# 7segement4digits1badidea-mk-2_0.net
KiCad netlist of a schematic drawn in EAGLE
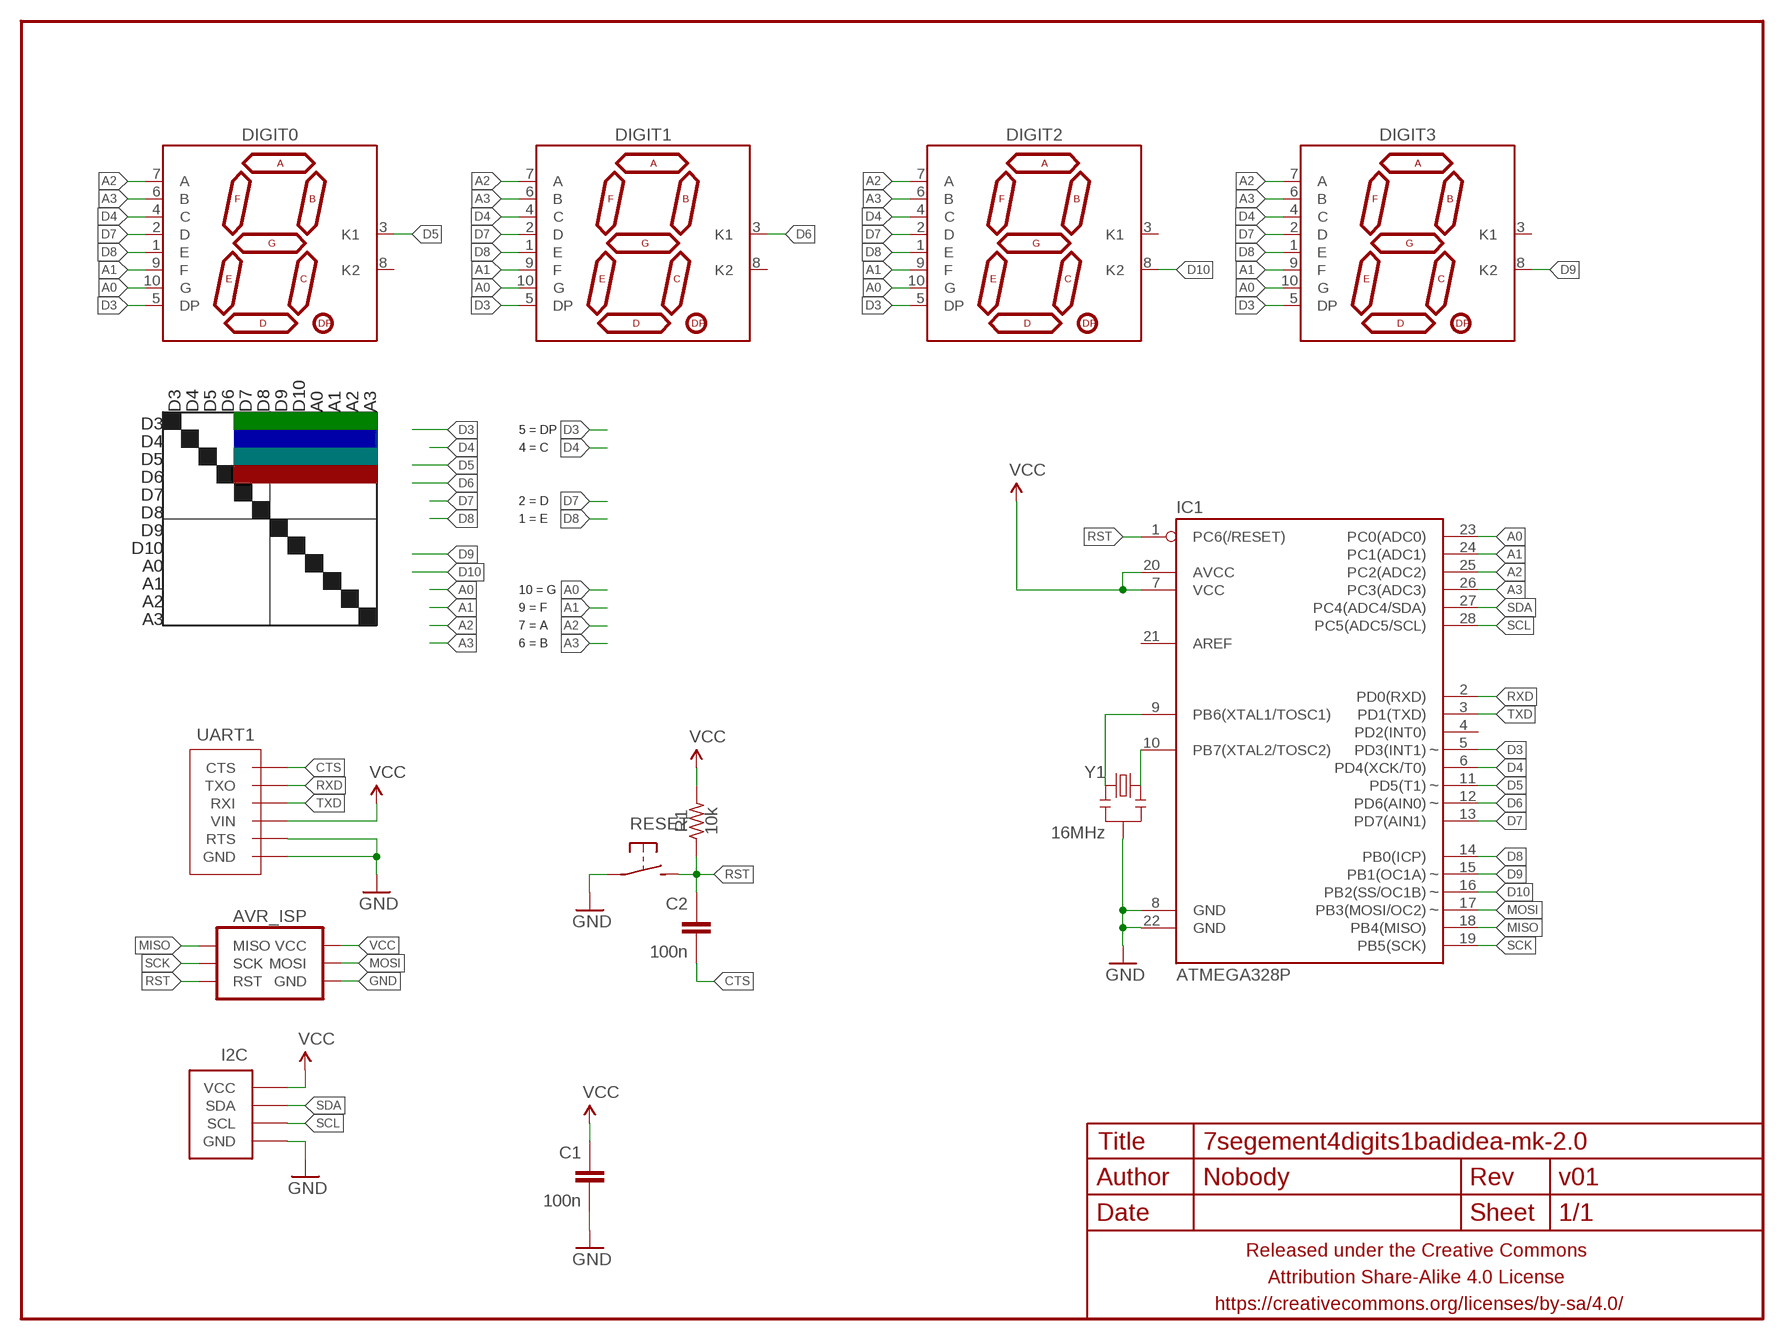
[diagram p0: schematic, sheet 1]

(export (version "E")
  (design (tool "Eeschema 10.0.6"))
  (components
    (comp (ref "AVR_ISP")
      (value "AVR_SPI_PRG_6PTH")
      (footprint "eagle-import:2X3")
      (libsource (lib "eagle-import") (part "AVR_SPI_PRG_6PTH"))
    )
    (comp (ref "C1")
      (value "100n")
      (footprint "eagle-import:C025-024X044")
      (libsource (lib "eagle-import") (part "CAPACITOR-CERAMIC025-024X044"))
    )
    (comp (ref "C2")
      (value "100n")
      (footprint "eagle-import:C025-024X044")
      (libsource (lib "eagle-import") (part "CAPACITOR-CERAMIC025-024X044"))
    )
    (comp (ref "DIGIT0")
      (value "7SEG_1DIGPTH-25.4MM")
      (footprint "eagle-import:7SEG_1DIG_25.4MM")
      (libsource (lib "eagle-import") (part "7SEG_1DIGPTH-25.4MM"))
    )
    (comp (ref "DIGIT1")
      (value "7SEG_1DIGPTH-25.4MM")
      (footprint "eagle-import:7SEG_1DIG_25.4MM")
      (libsource (lib "eagle-import") (part "7SEG_1DIGPTH-25.4MM"))
    )
    (comp (ref "DIGIT2")
      (value "7SEG_1DIGPTH-25.4MM")
      (footprint "eagle-import:7SEG_1DIG_25.4MM")
      (libsource (lib "eagle-import") (part "7SEG_1DIGPTH-25.4MM"))
    )
    (comp (ref "DIGIT3")
      (value "7SEG_1DIGPTH-25.4MM")
      (footprint "eagle-import:7SEG_1DIG_25.4MM")
      (libsource (lib "eagle-import") (part "7SEG_1DIGPTH-25.4MM"))
    )
    (comp (ref "FRAME1")
      (value "FRAME-LETTERNO_PACKAGE")
      (footprint "eagle-import:DUMMY")
      (fields (field (name "DESIGNER") "Nobody"))
      (libsource (lib "eagle-import") (part "FRAME-LETTERNO_PACKAGE"))
    )
    (comp (ref "I2C")
      (value "M04-I2CPTH-0.1IN-CENTERED-FLIPPED")
      (footprint "eagle-import:1X04-PTH-VERT-I2C-CENTERED-FLIPPED")
      (libsource (lib "eagle-import") (part "M04-I2CPTH-0.1IN-CENTERED-FLIPPED"))
    )
    (comp (ref "IC1")
      (value "ATMEGA328P")
      (footprint "eagle-import:DIL28-3")
      (libsource (lib "eagle-import") (part "ATMEGA328P_PDIP"))
    )
    (comp (ref "R1")
      (value "10k")
      (footprint "eagle-import:RESISTOR-AXIAL-PTH-7.62MM")
      (libsource (lib "eagle-import") (part "RESISTORPTH-AXIAL-7.62MM"))
    )
    (comp (ref "RESET")
      (value "SPST-NO-TACT3MM-PTH-SMALL-PADS")
      (footprint "eagle-import:DTS-3-SMALL-PADS")
      (libsource (lib "eagle-import") (part "SPST-NO-TACT3MM-PTH-SMALL-PADS"))
    )
    (comp (ref "UART1")
      (value "M06-UARTPTH-0.1IN")
      (footprint "eagle-import:1X06_PTH_UART")
      (libsource (lib "eagle-import") (part "M06-UARTPTH-0.1IN"))
    )
    (comp (ref "Y1")
      (value "16MHz")
      (footprint "eagle-import:RESONATOR-PTH")
      (libsource (lib "eagle-import") (part "RESONATORPTH"))
    )
  )
  (nets
    (net (code "1") (name "A0") (class "Default")
      (node (ref "DIGIT0") (pin "10") (pinfunction "G_10") (pintype "bidirectional"))
      (node (ref "DIGIT1") (pin "10") (pinfunction "G_10") (pintype "bidirectional"))
      (node (ref "DIGIT2") (pin "10") (pinfunction "G_10") (pintype "bidirectional"))
      (node (ref "DIGIT3") (pin "10") (pinfunction "G_10") (pintype "bidirectional"))
      (node (ref "IC1") (pin "23") (pinfunction "PC0(ADC0)_23") (pintype "bidirectional"))
    )
    (net (code "2") (name "A1") (class "Default")
      (node (ref "DIGIT0") (pin "9") (pinfunction "F_9") (pintype "bidirectional"))
      (node (ref "DIGIT1") (pin "9") (pinfunction "F_9") (pintype "bidirectional"))
      (node (ref "DIGIT2") (pin "9") (pinfunction "F_9") (pintype "bidirectional"))
      (node (ref "DIGIT3") (pin "9") (pinfunction "F_9") (pintype "bidirectional"))
      (node (ref "IC1") (pin "24") (pinfunction "PC1(ADC1)_24") (pintype "bidirectional"))
    )
    (net (code "3") (name "A2") (class "Default")
      (node (ref "DIGIT0") (pin "7") (pinfunction "A_7") (pintype "bidirectional"))
      (node (ref "DIGIT1") (pin "7") (pinfunction "A_7") (pintype "bidirectional"))
      (node (ref "DIGIT2") (pin "7") (pinfunction "A_7") (pintype "bidirectional"))
      (node (ref "DIGIT3") (pin "7") (pinfunction "A_7") (pintype "bidirectional"))
      (node (ref "IC1") (pin "25") (pinfunction "PC2(ADC2)_25") (pintype "bidirectional"))
    )
    (net (code "4") (name "A3") (class "Default")
      (node (ref "DIGIT0") (pin "6") (pinfunction "B_6") (pintype "bidirectional"))
      (node (ref "DIGIT1") (pin "6") (pinfunction "B_6") (pintype "bidirectional"))
      (node (ref "DIGIT2") (pin "6") (pinfunction "B_6") (pintype "bidirectional"))
      (node (ref "DIGIT3") (pin "6") (pinfunction "B_6") (pintype "bidirectional"))
      (node (ref "IC1") (pin "26") (pinfunction "PC3(ADC3)_26") (pintype "bidirectional"))
    )
    (net (code "5") (name "CTS") (class "Default")
      (node (ref "C2") (pin "2") (pinfunction "2_2") (pintype "passive"))
      (node (ref "UART1") (pin "CTS") (pinfunction "CTS_CTS") (pintype "bidirectional"))
    )
    (net (code "6") (name "D3") (class "Default")
      (node (ref "DIGIT0") (pin "5") (pinfunction "DP_5") (pintype "bidirectional"))
      (node (ref "DIGIT1") (pin "5") (pinfunction "DP_5") (pintype "bidirectional"))
      (node (ref "DIGIT2") (pin "5") (pinfunction "DP_5") (pintype "bidirectional"))
      (node (ref "DIGIT3") (pin "5") (pinfunction "DP_5") (pintype "bidirectional"))
      (node (ref "IC1") (pin "5") (pinfunction "PD3(INT1)_5") (pintype "bidirectional"))
    )
    (net (code "7") (name "D4") (class "Default")
      (node (ref "DIGIT0") (pin "4") (pinfunction "C_4") (pintype "bidirectional"))
      (node (ref "DIGIT1") (pin "4") (pinfunction "C_4") (pintype "bidirectional"))
      (node (ref "DIGIT2") (pin "4") (pinfunction "C_4") (pintype "bidirectional"))
      (node (ref "DIGIT3") (pin "4") (pinfunction "C_4") (pintype "bidirectional"))
      (node (ref "IC1") (pin "6") (pinfunction "PD4(XCK/T0)_6") (pintype "bidirectional"))
    )
    (net (code "8") (name "D5") (class "Default")
      (node (ref "DIGIT0") (pin "3") (pinfunction "K1_3") (pintype "bidirectional"))
      (node (ref "IC1") (pin "11") (pinfunction "PD5(T1)_11") (pintype "bidirectional"))
    )
    (net (code "9") (name "D6") (class "Default")
      (node (ref "DIGIT1") (pin "3") (pinfunction "K1_3") (pintype "bidirectional"))
      (node (ref "IC1") (pin "12") (pinfunction "PD6(AIN0)_12") (pintype "bidirectional"))
    )
    (net (code "10") (name "D7") (class "Default")
      (node (ref "DIGIT0") (pin "2") (pinfunction "D_2") (pintype "bidirectional"))
      (node (ref "DIGIT1") (pin "2") (pinfunction "D_2") (pintype "bidirectional"))
      (node (ref "DIGIT2") (pin "2") (pinfunction "D_2") (pintype "bidirectional"))
      (node (ref "DIGIT3") (pin "2") (pinfunction "D_2") (pintype "bidirectional"))
      (node (ref "IC1") (pin "13") (pinfunction "PD7(AIN1)_13") (pintype "bidirectional"))
    )
    (net (code "11") (name "D8") (class "Default")
      (node (ref "DIGIT0") (pin "1") (pinfunction "E_1") (pintype "bidirectional"))
      (node (ref "DIGIT1") (pin "1") (pinfunction "E_1") (pintype "bidirectional"))
      (node (ref "DIGIT2") (pin "1") (pinfunction "E_1") (pintype "bidirectional"))
      (node (ref "DIGIT3") (pin "1") (pinfunction "E_1") (pintype "bidirectional"))
      (node (ref "IC1") (pin "14") (pinfunction "PB0(ICP)_14") (pintype "bidirectional"))
    )
    (net (code "12") (name "D9") (class "Default")
      (node (ref "DIGIT3") (pin "8") (pinfunction "K2_8") (pintype "bidirectional"))
      (node (ref "IC1") (pin "15") (pinfunction "PB1(OC1A)_15") (pintype "bidirectional"))
    )
    (net (code "13") (name "D10") (class "Default")
      (node (ref "DIGIT2") (pin "8") (pinfunction "K2_8") (pintype "bidirectional"))
      (node (ref "IC1") (pin "16") (pinfunction "PB2(SS/OC1B)_16") (pintype "bidirectional"))
    )
    (net (code "14") (name "GND") (class "Default")
      (node (ref "AVR_ISP") (pin "6") (pinfunction "GND_6") (pintype "passive"))
      (node (ref "C1") (pin "2") (pinfunction "2_2") (pintype "passive"))
      (node (ref "I2C") (pin "GND") (pinfunction "GND_GND") (pintype "bidirectional"))
      (node (ref "IC1") (pin "22") (pinfunction "GND_22") (pintype "bidirectional"))
      (node (ref "IC1") (pin "8") (pinfunction "GND_8") (pintype "bidirectional"))
      (node (ref "RESET") (pin "1") (pinfunction "1_1") (pintype "passive"))
      (node (ref "UART1") (pin "GND") (pinfunction "GND_GND") (pintype "bidirectional"))
      (node (ref "UART1") (pin "RTS") (pinfunction "RTS_RTS") (pintype "bidirectional"))
      (node (ref "Y1") (pin "2") (pinfunction "2_2") (pintype "passive"))
    )
    (net (code "15") (name "MISO") (class "Default")
      (node (ref "AVR_ISP") (pin "1") (pinfunction "MISO_1") (pintype "passive"))
      (node (ref "IC1") (pin "18") (pinfunction "PB4(MISO)_18") (pintype "bidirectional"))
    )
    (net (code "16") (name "MOSI") (class "Default")
      (node (ref "AVR_ISP") (pin "4") (pinfunction "MOSI_4") (pintype "passive"))
      (node (ref "IC1") (pin "17") (pinfunction "PB3(MOSI/OC2)_17") (pintype "bidirectional"))
    )
    (net (code "17") (name "Net-(IC1-PB6(XTAL1{slash}TOSC1))") (class "Default")
      (node (ref "IC1") (pin "9") (pinfunction "PB6(XTAL1/TOSC1)_9") (pintype "bidirectional"))
      (node (ref "Y1") (pin "3") (pinfunction "3_3") (pintype "passive"))
    )
    (net (code "18") (name "Net-(IC1-PB7(XTAL2{slash}TOSC2))") (class "Default")
      (node (ref "IC1") (pin "10") (pinfunction "PB7(XTAL2/TOSC2)_10") (pintype "bidirectional"))
      (node (ref "Y1") (pin "1") (pinfunction "1_1") (pintype "passive"))
    )
    (net (code "19") (name "RST") (class "Default")
      (node (ref "AVR_ISP") (pin "5") (pinfunction "RST_5") (pintype "passive"))
      (node (ref "C2") (pin "1") (pinfunction "1_1") (pintype "passive"))
      (node (ref "IC1") (pin "1") (pinfunction "PC6(/RESET)_1") (pintype "bidirectional"))
      (node (ref "R1") (pin "P$1") (pinfunction "1_P$1") (pintype "passive"))
      (node (ref "RESET") (pin "2") (pinfunction "2_2") (pintype "passive"))
    )
    (net (code "20") (name "RXD") (class "Default")
      (node (ref "IC1") (pin "2") (pinfunction "PD0(RXD)_2") (pintype "bidirectional"))
      (node (ref "UART1") (pin "TXO") (pinfunction "TXO_TXO") (pintype "bidirectional"))
    )
    (net (code "21") (name "SCK") (class "Default")
      (node (ref "AVR_ISP") (pin "3") (pinfunction "SCK_3") (pintype "passive"))
      (node (ref "IC1") (pin "19") (pinfunction "PB5(SCK)_19") (pintype "bidirectional"))
    )
    (net (code "22") (name "SCL") (class "Default")
      (node (ref "I2C") (pin "SCL") (pinfunction "SCL_SCL") (pintype "bidirectional"))
      (node (ref "IC1") (pin "28") (pinfunction "PC5(ADC5/SCL)_28") (pintype "bidirectional"))
    )
    (net (code "23") (name "SDA") (class "Default")
      (node (ref "I2C") (pin "SDA") (pinfunction "SDA_SDA") (pintype "bidirectional"))
      (node (ref "IC1") (pin "27") (pinfunction "PC4(ADC4/SDA)_27") (pintype "bidirectional"))
    )
    (net (code "24") (name "TXD") (class "Default")
      (node (ref "IC1") (pin "3") (pinfunction "PD1(TXD)_3") (pintype "bidirectional"))
      (node (ref "UART1") (pin "RXI") (pinfunction "RXI_RXI") (pintype "bidirectional"))
    )
    (net (code "25") (name "VCC") (class "Default")
      (node (ref "AVR_ISP") (pin "2") (pinfunction "VCC_2") (pintype "passive"))
      (node (ref "C1") (pin "1") (pinfunction "1_1") (pintype "passive"))
      (node (ref "I2C") (pin "VCC") (pinfunction "VCC_VCC") (pintype "bidirectional"))
      (node (ref "IC1") (pin "20") (pinfunction "AVCC_20") (pintype "bidirectional"))
      (node (ref "IC1") (pin "7") (pinfunction "VCC_7") (pintype "bidirectional"))
      (node (ref "R1") (pin "P$2") (pinfunction "2_P$2") (pintype "passive"))
      (node (ref "UART1") (pin "VCC") (pinfunction "VIN_VCC") (pintype "bidirectional"))
    )
    (net (code "26") (name "unconnected-(DIGIT0-K2-Pad8)") (class "Default")
      (node (ref "DIGIT0") (pin "8") (pinfunction "K2_8") (pintype "bidirectional"))
    )
    (net (code "27") (name "unconnected-(DIGIT1-K2-Pad8)") (class "Default")
      (node (ref "DIGIT1") (pin "8") (pinfunction "K2_8") (pintype "bidirectional"))
    )
    (net (code "28") (name "unconnected-(DIGIT2-K1-Pad3)") (class "Default")
      (node (ref "DIGIT2") (pin "3") (pinfunction "K1_3") (pintype "bidirectional"))
    )
    (net (code "29") (name "unconnected-(DIGIT3-K1-Pad3)") (class "Default")
      (node (ref "DIGIT3") (pin "3") (pinfunction "K1_3") (pintype "bidirectional"))
    )
    (net (code "30") (name "unconnected-(IC1-AREF-Pad21)") (class "Default")
      (node (ref "IC1") (pin "21") (pinfunction "AREF_21") (pintype "bidirectional"))
    )
    (net (code "31") (name "unconnected-(IC1-PD2(INT0)-Pad4)") (class "Default")
      (node (ref "IC1") (pin "4") (pinfunction "PD2(INT0)_4") (pintype "bidirectional"))
    )
  )
)
